# LEDs.net
KiCad netlist of a schematic drawn in Altium Designer
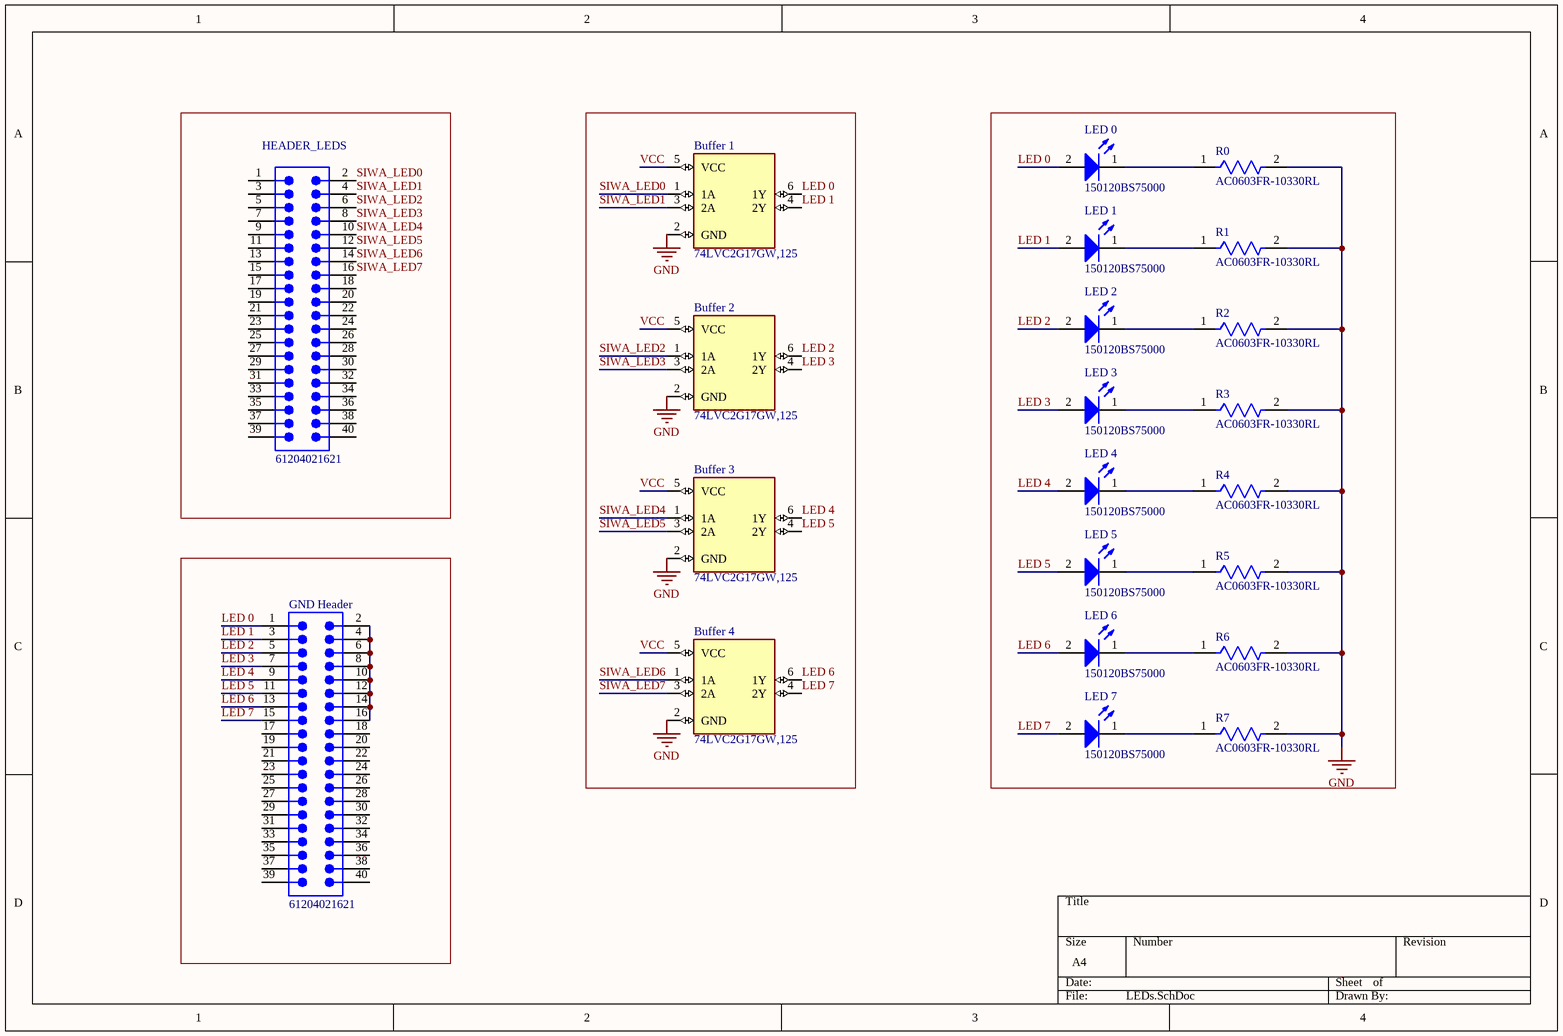
[diagram p0: LEDs.SchDoc]

(export (version "E")
  (design (tool "Eeschema 10.0.6"))
  (components
    (comp (ref "Buffer 1")
      (value "74LVC2G17GW,125")
      (footprint "SOT363_INFINEON")
      (description "Buffer, Non-Inverting 2 Element 1 Bit per Element Push-Pull Output 6-TSSOP")
      (fields (field (name "MF") "Nexperia USA"))
      (libsource (lib "74LVC2G17GW_125") (part "74LVC2G17GW,125"))
    )
    (comp (ref "Buffer 2")
      (value "74LVC2G17GW,125")
      (footprint "SOT363_INFINEON")
      (description "Buffer, Non-Inverting 2 Element 1 Bit per Element Push-Pull Output 6-TSSOP")
      (fields (field (name "MF") "Nexperia USA"))
      (libsource (lib "74LVC2G17GW_125") (part "74LVC2G17GW,125"))
    )
    (comp (ref "Buffer 3")
      (value "74LVC2G17GW,125")
      (footprint "SOT363_INFINEON")
      (description "Buffer, Non-Inverting 2 Element 1 Bit per Element Push-Pull Output 6-TSSOP")
      (fields (field (name "MF") "Nexperia USA"))
      (libsource (lib "74LVC2G17GW_125") (part "74LVC2G17GW,125"))
    )
    (comp (ref "Buffer 4")
      (value "74LVC2G17GW,125")
      (footprint "SOT363_INFINEON")
      (description "Buffer, Non-Inverting 2 Element 1 Bit per Element Push-Pull Output 6-TSSOP")
      (fields (field (name "MF") "Nexperia USA"))
      (libsource (lib "74LVC2G17GW_125") (part "74LVC2G17GW,125"))
    )
    (comp (ref "GND Header")
      (value "61204021621")
      (footprint "61204021621")
      (description "WR-BHD Straight Male, Box Header, Through Hole, 2 Rows, 40 Contacts, 2.54mm Pitch")
      (libsource (lib "Altium Content Vault") (part "Header_Male_2R_40P"))
    )
    (comp (ref "HEADER_LEDS")
      (value "61204021621")
      (footprint "61204021621")
      (description "WR-BHD Straight Male, Box Header, Through Hole, 2 Rows, 40 Contacts, 2.54mm Pitch")
      (libsource (lib "Altium Content Vault") (part "Header_Male_2R_40P"))
    )
    (comp (ref "LED 0")
      (value "150120BS75000")
      (footprint "WL-SMCW_1206_150120xx75000")
      (description "WL-SMCW SMT Mono-Color Chip LED Waterclear")
      (libsource (lib "Altium Content Vault") (part "LED_Blue_2A-1K"))
    )
    (comp (ref "LED 1")
      (value "150120BS75000")
      (footprint "WL-SMCW_1206_150120xx75000")
      (description "WL-SMCW SMT Mono-Color Chip LED Waterclear")
      (libsource (lib "Altium Content Vault") (part "LED_Blue_2A-1K"))
    )
    (comp (ref "LED 2")
      (value "150120BS75000")
      (footprint "WL-SMCW_1206_150120xx75000")
      (description "WL-SMCW SMT Mono-Color Chip LED Waterclear")
      (libsource (lib "Altium Content Vault") (part "LED_Blue_2A-1K"))
    )
    (comp (ref "LED 3")
      (value "150120BS75000")
      (footprint "WL-SMCW_1206_150120xx75000")
      (description "WL-SMCW SMT Mono-Color Chip LED Waterclear")
      (libsource (lib "Altium Content Vault") (part "LED_Blue_2A-1K"))
    )
    (comp (ref "LED 4")
      (value "150120BS75000")
      (footprint "WL-SMCW_1206_150120xx75000")
      (description "WL-SMCW SMT Mono-Color Chip LED Waterclear")
      (libsource (lib "Altium Content Vault") (part "LED_Blue_2A-1K"))
    )
    (comp (ref "LED 5")
      (value "150120BS75000")
      (footprint "WL-SMCW_1206_150120xx75000")
      (description "WL-SMCW SMT Mono-Color Chip LED Waterclear")
      (libsource (lib "Altium Content Vault") (part "LED_Blue_2A-1K"))
    )
    (comp (ref "LED 6")
      (value "150120BS75000")
      (footprint "WL-SMCW_1206_150120xx75000")
      (description "WL-SMCW SMT Mono-Color Chip LED Waterclear")
      (libsource (lib "Altium Content Vault") (part "LED_Blue_2A-1K"))
    )
    (comp (ref "LED 7")
      (value "150120BS75000")
      (footprint "WL-SMCW_1206_150120xx75000")
      (description "WL-SMCW SMT Mono-Color Chip LED Waterclear")
      (libsource (lib "Altium Content Vault") (part "LED_Blue_2A-1K"))
    )
    (comp (ref "R0")
      (value "AC0603FR-10330RL")
      (footprint "FP-AC0603-IPC_A")
      (description "RES 330Ω 1.00% 0.1W 0603")
      (libsource (lib "Altium Content Vault") (part "1029c3af85768c4190bb7ad29bc67b5"))
    )
    (comp (ref "R1")
      (value "AC0603FR-10330RL")
      (footprint "FP-AC0603-IPC_A")
      (description "RES 330Ω 1.00% 0.1W 0603")
      (libsource (lib "Altium Content Vault") (part "1029c3af85768c4190bb7ad29bc67b5"))
    )
    (comp (ref "R2")
      (value "AC0603FR-10330RL")
      (footprint "FP-AC0603-IPC_A")
      (description "RES 330Ω 1.00% 0.1W 0603")
      (libsource (lib "Altium Content Vault") (part "1029c3af85768c4190bb7ad29bc67b5"))
    )
    (comp (ref "R3")
      (value "AC0603FR-10330RL")
      (footprint "FP-AC0603-IPC_A")
      (description "RES 330Ω 1.00% 0.1W 0603")
      (libsource (lib "Altium Content Vault") (part "1029c3af85768c4190bb7ad29bc67b5"))
    )
    (comp (ref "R4")
      (value "AC0603FR-10330RL")
      (footprint "FP-AC0603-IPC_A")
      (description "RES 330Ω 1.00% 0.1W 0603")
      (libsource (lib "Altium Content Vault") (part "1029c3af85768c4190bb7ad29bc67b5"))
    )
    (comp (ref "R5")
      (value "AC0603FR-10330RL")
      (footprint "FP-AC0603-IPC_A")
      (description "RES 330Ω 1.00% 0.1W 0603")
      (libsource (lib "Altium Content Vault") (part "1029c3af85768c4190bb7ad29bc67b5"))
    )
    (comp (ref "R6")
      (value "AC0603FR-10330RL")
      (footprint "FP-AC0603-IPC_A")
      (description "RES 330Ω 1.00% 0.1W 0603")
      (libsource (lib "Altium Content Vault") (part "1029c3af85768c4190bb7ad29bc67b5"))
    )
    (comp (ref "R7")
      (value "AC0603FR-10330RL")
      (footprint "FP-AC0603-IPC_A")
      (description "RES 330Ω 1.00% 0.1W 0603")
      (libsource (lib "Altium Content Vault") (part "1029c3af85768c4190bb7ad29bc67b5"))
    )
  )
  (nets
    (net (code "1") (name "/LED 0") (class "Default")
      (node (ref "Buffer 1") (pin "6") (pinfunction "1Y_6") (pintype "bidirectional"))
      (node (ref "GND Header") (pin "1") (pinfunction "1_1") (pintype "passive"))
      (node (ref "LED 0") (pin "2") (pinfunction "A_2") (pintype "passive"))
    )
    (net (code "2") (name "/LED 1") (class "Default")
      (node (ref "Buffer 1") (pin "4") (pinfunction "2Y_4") (pintype "bidirectional"))
      (node (ref "GND Header") (pin "3") (pinfunction "3_3") (pintype "passive"))
      (node (ref "LED 1") (pin "2") (pinfunction "A_2") (pintype "passive"))
    )
    (net (code "3") (name "/LED 2") (class "Default")
      (node (ref "Buffer 2") (pin "6") (pinfunction "1Y_6") (pintype "bidirectional"))
      (node (ref "GND Header") (pin "5") (pinfunction "5_5") (pintype "passive"))
      (node (ref "LED 2") (pin "2") (pinfunction "A_2") (pintype "passive"))
    )
    (net (code "4") (name "/LED 3") (class "Default")
      (node (ref "Buffer 2") (pin "4") (pinfunction "2Y_4") (pintype "bidirectional"))
      (node (ref "GND Header") (pin "7") (pinfunction "7_7") (pintype "passive"))
      (node (ref "LED 3") (pin "2") (pinfunction "A_2") (pintype "passive"))
    )
    (net (code "5") (name "/LED 4") (class "Default")
      (node (ref "Buffer 3") (pin "6") (pinfunction "1Y_6") (pintype "bidirectional"))
      (node (ref "GND Header") (pin "9") (pinfunction "9_9") (pintype "passive"))
      (node (ref "LED 4") (pin "2") (pinfunction "A_2") (pintype "passive"))
    )
    (net (code "6") (name "/LED 5") (class "Default")
      (node (ref "Buffer 3") (pin "4") (pinfunction "2Y_4") (pintype "bidirectional"))
      (node (ref "GND Header") (pin "11") (pinfunction "11_11") (pintype "passive"))
      (node (ref "LED 5") (pin "2") (pinfunction "A_2") (pintype "passive"))
    )
    (net (code "7") (name "/LED 6") (class "Default")
      (node (ref "Buffer 4") (pin "6") (pinfunction "1Y_6") (pintype "bidirectional"))
      (node (ref "GND Header") (pin "13") (pinfunction "13_13") (pintype "passive"))
      (node (ref "LED 6") (pin "2") (pinfunction "A_2") (pintype "passive"))
    )
    (net (code "8") (name "/LED 7") (class "Default")
      (node (ref "Buffer 4") (pin "4") (pinfunction "2Y_4") (pintype "bidirectional"))
      (node (ref "GND Header") (pin "15") (pinfunction "15_15") (pintype "passive"))
      (node (ref "LED 7") (pin "2") (pinfunction "A_2") (pintype "passive"))
    )
    (net (code "9") (name "/SIWA_LED0") (class "Default")
      (node (ref "Buffer 1") (pin "1") (pinfunction "1A_1") (pintype "bidirectional"))
      (node (ref "HEADER_LEDS") (pin "2") (pinfunction "2_2") (pintype "passive"))
    )
    (net (code "10") (name "/SIWA_LED1") (class "Default")
      (node (ref "Buffer 1") (pin "3") (pinfunction "2A_3") (pintype "bidirectional"))
      (node (ref "HEADER_LEDS") (pin "4") (pinfunction "4_4") (pintype "passive"))
    )
    (net (code "11") (name "/SIWA_LED2") (class "Default")
      (node (ref "Buffer 2") (pin "1") (pinfunction "1A_1") (pintype "bidirectional"))
      (node (ref "HEADER_LEDS") (pin "6") (pinfunction "6_6") (pintype "passive"))
    )
    (net (code "12") (name "/SIWA_LED3") (class "Default")
      (node (ref "Buffer 2") (pin "3") (pinfunction "2A_3") (pintype "bidirectional"))
      (node (ref "HEADER_LEDS") (pin "8") (pinfunction "8_8") (pintype "passive"))
    )
    (net (code "13") (name "/SIWA_LED4") (class "Default")
      (node (ref "Buffer 3") (pin "1") (pinfunction "1A_1") (pintype "bidirectional"))
      (node (ref "HEADER_LEDS") (pin "10") (pinfunction "10_10") (pintype "passive"))
    )
    (net (code "14") (name "/SIWA_LED5") (class "Default")
      (node (ref "Buffer 3") (pin "3") (pinfunction "2A_3") (pintype "bidirectional"))
      (node (ref "HEADER_LEDS") (pin "12") (pinfunction "12_12") (pintype "passive"))
    )
    (net (code "15") (name "/SIWA_LED6") (class "Default")
      (node (ref "Buffer 4") (pin "1") (pinfunction "1A_1") (pintype "bidirectional"))
      (node (ref "HEADER_LEDS") (pin "14") (pinfunction "14_14") (pintype "passive"))
    )
    (net (code "16") (name "/SIWA_LED7") (class "Default")
      (node (ref "Buffer 4") (pin "3") (pinfunction "2A_3") (pintype "bidirectional"))
      (node (ref "HEADER_LEDS") (pin "16") (pinfunction "16_16") (pintype "passive"))
    )
    (net (code "17") (name "/VCC") (class "Default")
      (node (ref "Buffer 1") (pin "5") (pinfunction "VCC_5") (pintype "bidirectional"))
      (node (ref "Buffer 2") (pin "5") (pinfunction "VCC_5") (pintype "bidirectional"))
      (node (ref "Buffer 3") (pin "5") (pinfunction "VCC_5") (pintype "bidirectional"))
      (node (ref "Buffer 4") (pin "5") (pinfunction "VCC_5") (pintype "bidirectional"))
    )
    (net (code "18") (name "GND") (class "Default")
      (node (ref "Buffer 1") (pin "2") (pinfunction "GND_2") (pintype "bidirectional"))
      (node (ref "Buffer 2") (pin "2") (pinfunction "GND_2") (pintype "bidirectional"))
      (node (ref "Buffer 3") (pin "2") (pinfunction "GND_2") (pintype "bidirectional"))
      (node (ref "Buffer 4") (pin "2") (pinfunction "GND_2") (pintype "bidirectional"))
      (node (ref "R0") (pin "2") (pinfunction "2_2") (pintype "passive"))
      (node (ref "R1") (pin "2") (pinfunction "2_2") (pintype "passive"))
      (node (ref "R2") (pin "2") (pinfunction "2_2") (pintype "passive"))
      (node (ref "R3") (pin "2") (pinfunction "2_2") (pintype "passive"))
      (node (ref "R4") (pin "2") (pinfunction "2_2") (pintype "passive"))
      (node (ref "R5") (pin "2") (pinfunction "2_2") (pintype "passive"))
      (node (ref "R6") (pin "2") (pinfunction "2_2") (pintype "passive"))
      (node (ref "R7") (pin "2") (pinfunction "2_2") (pintype "passive"))
    )
    (net (code "19") (name "Net-(GND Header-Pad10)") (class "Default")
      (node (ref "GND Header") (pin "10") (pinfunction "10_10") (pintype "passive"))
      (node (ref "GND Header") (pin "12") (pinfunction "12_12") (pintype "passive"))
      (node (ref "GND Header") (pin "14") (pinfunction "14_14") (pintype "passive"))
      (node (ref "GND Header") (pin "16") (pinfunction "16_16") (pintype "passive"))
      (node (ref "GND Header") (pin "2") (pinfunction "2_2") (pintype "passive"))
      (node (ref "GND Header") (pin "4") (pinfunction "4_4") (pintype "passive"))
      (node (ref "GND Header") (pin "6") (pinfunction "6_6") (pintype "passive"))
      (node (ref "GND Header") (pin "8") (pinfunction "8_8") (pintype "passive"))
    )
    (net (code "20") (name "Net-(LED 0-K)") (class "Default")
      (node (ref "LED 0") (pin "1") (pinfunction "K_1") (pintype "passive"))
      (node (ref "R0") (pin "1") (pinfunction "1_1") (pintype "passive"))
    )
    (net (code "21") (name "Net-(LED 1-K)") (class "Default")
      (node (ref "LED 1") (pin "1") (pinfunction "K_1") (pintype "passive"))
      (node (ref "R1") (pin "1") (pinfunction "1_1") (pintype "passive"))
    )
    (net (code "22") (name "Net-(LED 2-K)") (class "Default")
      (node (ref "LED 2") (pin "1") (pinfunction "K_1") (pintype "passive"))
      (node (ref "R2") (pin "1") (pinfunction "1_1") (pintype "passive"))
    )
    (net (code "23") (name "Net-(LED 3-K)") (class "Default")
      (node (ref "LED 3") (pin "1") (pinfunction "K_1") (pintype "passive"))
      (node (ref "R3") (pin "1") (pinfunction "1_1") (pintype "passive"))
    )
    (net (code "24") (name "Net-(LED 4-K)") (class "Default")
      (node (ref "LED 4") (pin "1") (pinfunction "K_1") (pintype "passive"))
      (node (ref "R4") (pin "1") (pinfunction "1_1") (pintype "passive"))
    )
    (net (code "25") (name "Net-(LED 5-K)") (class "Default")
      (node (ref "LED 5") (pin "1") (pinfunction "K_1") (pintype "passive"))
      (node (ref "R5") (pin "1") (pinfunction "1_1") (pintype "passive"))
    )
    (net (code "26") (name "Net-(LED 6-K)") (class "Default")
      (node (ref "LED 6") (pin "1") (pinfunction "K_1") (pintype "passive"))
      (node (ref "R6") (pin "1") (pinfunction "1_1") (pintype "passive"))
    )
    (net (code "27") (name "Net-(LED 7-K)") (class "Default")
      (node (ref "LED 7") (pin "1") (pinfunction "K_1") (pintype "passive"))
      (node (ref "R7") (pin "1") (pinfunction "1_1") (pintype "passive"))
    )
    (net (code "28") (name "unconnected-(GND Header-Pad17)") (class "Default")
      (node (ref "GND Header") (pin "17") (pinfunction "17_17") (pintype "passive"))
    )
    (net (code "29") (name "unconnected-(GND Header-Pad18)") (class "Default")
      (node (ref "GND Header") (pin "18") (pinfunction "18_18") (pintype "passive"))
    )
    (net (code "30") (name "unconnected-(GND Header-Pad19)") (class "Default")
      (node (ref "GND Header") (pin "19") (pinfunction "19_19") (pintype "passive"))
    )
    (net (code "31") (name "unconnected-(GND Header-Pad20)") (class "Default")
      (node (ref "GND Header") (pin "20") (pinfunction "20_20") (pintype "passive"))
    )
    (net (code "32") (name "unconnected-(GND Header-Pad21)") (class "Default")
      (node (ref "GND Header") (pin "21") (pinfunction "21_21") (pintype "passive"))
    )
    (net (code "33") (name "unconnected-(GND Header-Pad22)") (class "Default")
      (node (ref "GND Header") (pin "22") (pinfunction "22_22") (pintype "passive"))
    )
    (net (code "34") (name "unconnected-(GND Header-Pad23)") (class "Default")
      (node (ref "GND Header") (pin "23") (pinfunction "23_23") (pintype "passive"))
    )
    (net (code "35") (name "unconnected-(GND Header-Pad24)") (class "Default")
      (node (ref "GND Header") (pin "24") (pinfunction "24_24") (pintype "passive"))
    )
    (net (code "36") (name "unconnected-(GND Header-Pad25)") (class "Default")
      (node (ref "GND Header") (pin "25") (pinfunction "25_25") (pintype "passive"))
    )
    (net (code "37") (name "unconnected-(GND Header-Pad26)") (class "Default")
      (node (ref "GND Header") (pin "26") (pinfunction "26_26") (pintype "passive"))
    )
    (net (code "38") (name "unconnected-(GND Header-Pad27)") (class "Default")
      (node (ref "GND Header") (pin "27") (pinfunction "27_27") (pintype "passive"))
    )
    (net (code "39") (name "unconnected-(GND Header-Pad28)") (class "Default")
      (node (ref "GND Header") (pin "28") (pinfunction "28_28") (pintype "passive"))
    )
    (net (code "40") (name "unconnected-(GND Header-Pad29)") (class "Default")
      (node (ref "GND Header") (pin "29") (pinfunction "29_29") (pintype "passive"))
    )
    (net (code "41") (name "unconnected-(GND Header-Pad30)") (class "Default")
      (node (ref "GND Header") (pin "30") (pinfunction "30_30") (pintype "passive"))
    )
    (net (code "42") (name "unconnected-(GND Header-Pad31)") (class "Default")
      (node (ref "GND Header") (pin "31") (pinfunction "31_31") (pintype "passive"))
    )
    (net (code "43") (name "unconnected-(GND Header-Pad32)") (class "Default")
      (node (ref "GND Header") (pin "32") (pinfunction "32_32") (pintype "passive"))
    )
    (net (code "44") (name "unconnected-(GND Header-Pad33)") (class "Default")
      (node (ref "GND Header") (pin "33") (pinfunction "33_33") (pintype "passive"))
    )
    (net (code "45") (name "unconnected-(GND Header-Pad34)") (class "Default")
      (node (ref "GND Header") (pin "34") (pinfunction "34_34") (pintype "passive"))
    )
    (net (code "46") (name "unconnected-(GND Header-Pad35)") (class "Default")
      (node (ref "GND Header") (pin "35") (pinfunction "35_35") (pintype "passive"))
    )
    (net (code "47") (name "unconnected-(GND Header-Pad36)") (class "Default")
      (node (ref "GND Header") (pin "36") (pinfunction "36_36") (pintype "passive"))
    )
    (net (code "48") (name "unconnected-(GND Header-Pad37)") (class "Default")
      (node (ref "GND Header") (pin "37") (pinfunction "37_37") (pintype "passive"))
    )
    (net (code "49") (name "unconnected-(GND Header-Pad38)") (class "Default")
      (node (ref "GND Header") (pin "38") (pinfunction "38_38") (pintype "passive"))
    )
    (net (code "50") (name "unconnected-(GND Header-Pad39)") (class "Default")
      (node (ref "GND Header") (pin "39") (pinfunction "39_39") (pintype "passive"))
    )
    (net (code "51") (name "unconnected-(GND Header-Pad40)") (class "Default")
      (node (ref "GND Header") (pin "40") (pinfunction "40_40") (pintype "passive"))
    )
    (net (code "52") (name "unconnected-(HEADER_LEDS-Pad1)") (class "Default")
      (node (ref "HEADER_LEDS") (pin "1") (pinfunction "1_1") (pintype "passive"))
    )
    (net (code "53") (name "unconnected-(HEADER_LEDS-Pad3)") (class "Default")
      (node (ref "HEADER_LEDS") (pin "3") (pinfunction "3_3") (pintype "passive"))
    )
    (net (code "54") (name "unconnected-(HEADER_LEDS-Pad5)") (class "Default")
      (node (ref "HEADER_LEDS") (pin "5") (pinfunction "5_5") (pintype "passive"))
    )
    (net (code "55") (name "unconnected-(HEADER_LEDS-Pad7)") (class "Default")
      (node (ref "HEADER_LEDS") (pin "7") (pinfunction "7_7") (pintype "passive"))
    )
    (net (code "56") (name "unconnected-(HEADER_LEDS-Pad9)") (class "Default")
      (node (ref "HEADER_LEDS") (pin "9") (pinfunction "9_9") (pintype "passive"))
    )
    (net (code "57") (name "unconnected-(HEADER_LEDS-Pad11)") (class "Default")
      (node (ref "HEADER_LEDS") (pin "11") (pinfunction "11_11") (pintype "passive"))
    )
    (net (code "58") (name "unconnected-(HEADER_LEDS-Pad13)") (class "Default")
      (node (ref "HEADER_LEDS") (pin "13") (pinfunction "13_13") (pintype "passive"))
    )
    (net (code "59") (name "unconnected-(HEADER_LEDS-Pad15)") (class "Default")
      (node (ref "HEADER_LEDS") (pin "15") (pinfunction "15_15") (pintype "passive"))
    )
    (net (code "60") (name "unconnected-(HEADER_LEDS-Pad17)") (class "Default")
      (node (ref "HEADER_LEDS") (pin "17") (pinfunction "17_17") (pintype "passive"))
    )
    (net (code "61") (name "unconnected-(HEADER_LEDS-Pad18)") (class "Default")
      (node (ref "HEADER_LEDS") (pin "18") (pinfunction "18_18") (pintype "passive"))
    )
    (net (code "62") (name "unconnected-(HEADER_LEDS-Pad19)") (class "Default")
      (node (ref "HEADER_LEDS") (pin "19") (pinfunction "19_19") (pintype "passive"))
    )
    (net (code "63") (name "unconnected-(HEADER_LEDS-Pad20)") (class "Default")
      (node (ref "HEADER_LEDS") (pin "20") (pinfunction "20_20") (pintype "passive"))
    )
    (net (code "64") (name "unconnected-(HEADER_LEDS-Pad21)") (class "Default")
      (node (ref "HEADER_LEDS") (pin "21") (pinfunction "21_21") (pintype "passive"))
    )
    (net (code "65") (name "unconnected-(HEADER_LEDS-Pad22)") (class "Default")
      (node (ref "HEADER_LEDS") (pin "22") (pinfunction "22_22") (pintype "passive"))
    )
    (net (code "66") (name "unconnected-(HEADER_LEDS-Pad23)") (class "Default")
      (node (ref "HEADER_LEDS") (pin "23") (pinfunction "23_23") (pintype "passive"))
    )
    (net (code "67") (name "unconnected-(HEADER_LEDS-Pad24)") (class "Default")
      (node (ref "HEADER_LEDS") (pin "24") (pinfunction "24_24") (pintype "passive"))
    )
    (net (code "68") (name "unconnected-(HEADER_LEDS-Pad25)") (class "Default")
      (node (ref "HEADER_LEDS") (pin "25") (pinfunction "25_25") (pintype "passive"))
    )
    (net (code "69") (name "unconnected-(HEADER_LEDS-Pad26)") (class "Default")
      (node (ref "HEADER_LEDS") (pin "26") (pinfunction "26_26") (pintype "passive"))
    )
    (net (code "70") (name "unconnected-(HEADER_LEDS-Pad27)") (class "Default")
      (node (ref "HEADER_LEDS") (pin "27") (pinfunction "27_27") (pintype "passive"))
    )
    (net (code "71") (name "unconnected-(HEADER_LEDS-Pad28)") (class "Default")
      (node (ref "HEADER_LEDS") (pin "28") (pinfunction "28_28") (pintype "passive"))
    )
    (net (code "72") (name "unconnected-(HEADER_LEDS-Pad29)") (class "Default")
      (node (ref "HEADER_LEDS") (pin "29") (pinfunction "29_29") (pintype "passive"))
    )
    (net (code "73") (name "unconnected-(HEADER_LEDS-Pad30)") (class "Default")
      (node (ref "HEADER_LEDS") (pin "30") (pinfunction "30_30") (pintype "passive"))
    )
    (net (code "74") (name "unconnected-(HEADER_LEDS-Pad31)") (class "Default")
      (node (ref "HEADER_LEDS") (pin "31") (pinfunction "31_31") (pintype "passive"))
    )
    (net (code "75") (name "unconnected-(HEADER_LEDS-Pad32)") (class "Default")
      (node (ref "HEADER_LEDS") (pin "32") (pinfunction "32_32") (pintype "passive"))
    )
    (net (code "76") (name "unconnected-(HEADER_LEDS-Pad33)") (class "Default")
      (node (ref "HEADER_LEDS") (pin "33") (pinfunction "33_33") (pintype "passive"))
    )
    (net (code "77") (name "unconnected-(HEADER_LEDS-Pad34)") (class "Default")
      (node (ref "HEADER_LEDS") (pin "34") (pinfunction "34_34") (pintype "passive"))
    )
    (net (code "78") (name "unconnected-(HEADER_LEDS-Pad35)") (class "Default")
      (node (ref "HEADER_LEDS") (pin "35") (pinfunction "35_35") (pintype "passive"))
    )
    (net (code "79") (name "unconnected-(HEADER_LEDS-Pad36)") (class "Default")
      (node (ref "HEADER_LEDS") (pin "36") (pinfunction "36_36") (pintype "passive"))
    )
    (net (code "80") (name "unconnected-(HEADER_LEDS-Pad37)") (class "Default")
      (node (ref "HEADER_LEDS") (pin "37") (pinfunction "37_37") (pintype "passive"))
    )
    (net (code "81") (name "unconnected-(HEADER_LEDS-Pad38)") (class "Default")
      (node (ref "HEADER_LEDS") (pin "38") (pinfunction "38_38") (pintype "passive"))
    )
    (net (code "82") (name "unconnected-(HEADER_LEDS-Pad39)") (class "Default")
      (node (ref "HEADER_LEDS") (pin "39") (pinfunction "39_39") (pintype "passive"))
    )
    (net (code "83") (name "unconnected-(HEADER_LEDS-Pad40)") (class "Default")
      (node (ref "HEADER_LEDS") (pin "40") (pinfunction "40_40") (pintype "passive"))
    )
  )
)
